# Temporizador_555_r00.net
KiCad netlist of a schematic drawn in EAGLE
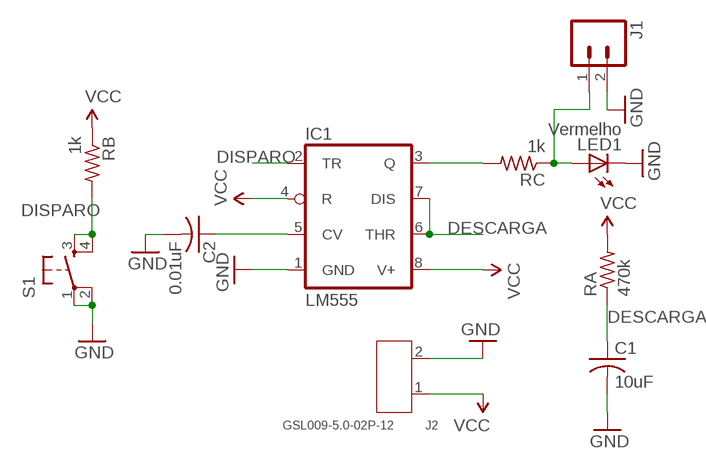
[diagram p0: schematic, sheet 1]

(export (version "E")
  (design (tool "Eeschema 10.0.6"))
  (components
    (comp (ref "C1")
      (value "10uF")
      (footprint "eagle-import:C050-024X044")
      (libsource (lib "eagle-import") (part "C-US050-024X044"))
    )
    (comp (ref "C2")
      (value "0.01uF")
      (footprint "eagle-import:C050-024X044")
      (libsource (lib "eagle-import") (part "C-US050-024X044"))
    )
    (comp (ref "IC1")
      (value "LM555")
      (footprint "eagle-import:DIL08-ROUND")
      (libsource (lib "eagle-import") (part "555NLM"))
    )
    (comp (ref "J1")
      (value "M02PTH")
      (footprint "eagle-import:1X02")
      (libsource (lib "eagle-import") (part "M02PTH"))
    )
    (comp (ref "J2")
      (value "GSL009-5.0-02P-12")
      (footprint "eagle-import:H2-5.0-10.5X8.0MM")
      (libsource (lib "eagle-import") (part "SCREW-TERMINAL-BLUE(2P-5.0)"))
    )
    (comp (ref "LED1")
      (value "Vermelho")
      (footprint "eagle-import:LED5MM")
      (libsource (lib "eagle-import") (part "LED5MM"))
    )
    (comp (ref "RA")
      (value "470k")
      (footprint "eagle-import:0207_10")
      (libsource (lib "eagle-import") (part "R-US_0207/10"))
    )
    (comp (ref "RB")
      (value "1k")
      (footprint "eagle-import:0207_10")
      (libsource (lib "eagle-import") (part "R-US_0207/10"))
    )
    (comp (ref "RC")
      (value "1k")
      (footprint "eagle-import:0207_10")
      (libsource (lib "eagle-import") (part "R-US_0207/10"))
    )
    (comp (ref "S1")
      (value "TACTILE-SWITCH-PTH")
      (footprint "eagle-import:TAC-SWITCH-PTH")
      (libsource (lib "eagle-import") (part "TACTILE-SWITCH-PTH"))
    )
  )
  (nets
    (net (code "1") (name "/DESCARGA") (class "Default")
      (node (ref "C1") (pin "1") (pinfunction "1_1") (pintype "passive"))
      (node (ref "IC1") (pin "6") (pinfunction "THR_6") (pintype "input"))
      (node (ref "IC1") (pin "7") (pinfunction "DIS_7") (pintype "input"))
      (node (ref "RA") (pin "1") (pinfunction "1_1") (pintype "passive"))
    )
    (net (code "2") (name "/DISPARO") (class "Default")
      (node (ref "IC1") (pin "2") (pinfunction "TR_2") (pintype "input"))
      (node (ref "RB") (pin "2") (pinfunction "2_2") (pintype "passive"))
      (node (ref "S1") (pin "3") (pinfunction "3_3") (pintype "passive"))
      (node (ref "S1") (pin "4") (pinfunction "4_4") (pintype "passive"))
    )
    (net (code "3") (name "GND") (class "Default")
      (node (ref "C1") (pin "2") (pinfunction "2_2") (pintype "passive"))
      (node (ref "C2") (pin "2") (pinfunction "2_2") (pintype "passive"))
      (node (ref "IC1") (pin "1") (pinfunction "GND_1") (pintype "power_in"))
      (node (ref "J1") (pin "2") (pinfunction "2_2") (pintype "passive"))
      (node (ref "J2") (pin "2") (pinfunction "2_2") (pintype "bidirectional"))
      (node (ref "LED1") (pin "K") (pinfunction "C_K") (pintype "passive"))
      (node (ref "S1") (pin "1") (pinfunction "1_1") (pintype "passive"))
      (node (ref "S1") (pin "2") (pinfunction "2_2") (pintype "passive"))
    )
    (net (code "4") (name "Net-(IC1-CV)") (class "Default")
      (node (ref "C2") (pin "1") (pinfunction "1_1") (pintype "passive"))
      (node (ref "IC1") (pin "5") (pinfunction "CV_5") (pintype "input"))
    )
    (net (code "5") (name "Net-(IC1-Q)") (class "Default")
      (node (ref "IC1") (pin "3") (pinfunction "Q_3") (pintype "output"))
      (node (ref "RC") (pin "2") (pinfunction "2_2") (pintype "passive"))
    )
    (net (code "6") (name "Net-(J1-Pad1)") (class "Default")
      (node (ref "J1") (pin "1") (pinfunction "1_1") (pintype "passive"))
      (node (ref "LED1") (pin "A") (pinfunction "A_A") (pintype "passive"))
      (node (ref "RC") (pin "1") (pinfunction "1_1") (pintype "passive"))
    )
    (net (code "7") (name "VCC") (class "Default")
      (node (ref "IC1") (pin "4") (pinfunction "R_4") (pintype "input"))
      (node (ref "IC1") (pin "8") (pinfunction "V+_8") (pintype "power_in"))
      (node (ref "J2") (pin "1") (pinfunction "1_1") (pintype "bidirectional"))
      (node (ref "RA") (pin "2") (pinfunction "2_2") (pintype "passive"))
      (node (ref "RB") (pin "1") (pinfunction "1_1") (pintype "passive"))
    )
  )
)
